# Connector.net
KiCad netlist of a schematic drawn in Altium Designer
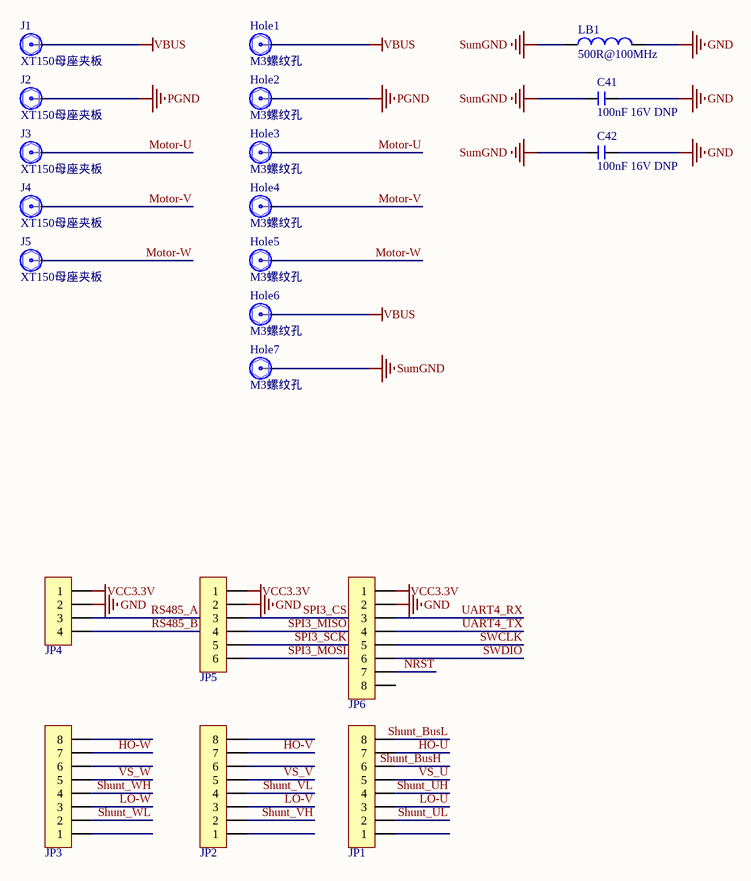
[diagram p0: Connector.SchDoc]

(export (version "E")
  (design (tool "Eeschema 10.0.6"))
  (components
    (comp (ref "C41")
      (value "100nF 16V DNP")
      (footprint "C0603_L")
      (description "独石电容")
      (fields (field (name "版权归属") "源创客"))
      (libsource (lib "Capacitor") (part "C-MLCC"))
    )
    (comp (ref "C42")
      (value "100nF 16V DNP")
      (footprint "C0603_L")
      (description "独石电容")
      (fields (field (name "版权归属") "源创客"))
      (libsource (lib "Capacitor") (part "C-MLCC"))
    )
    (comp (ref "Hole1") (value "M3螺纹孔") (footprint "M3_3*7载流孔_铜柱") (libsource (lib "Hole") (part "M3螺纹孔")))
    (comp (ref "Hole2") (value "M3螺纹孔") (footprint "M3_3*7载流孔_铜柱") (libsource (lib "Hole") (part "M3螺纹孔")))
    (comp (ref "Hole3") (value "M3螺纹孔") (footprint "M3_3*7载流孔_螺丝") (libsource (lib "Hole") (part "M3螺纹孔")))
    (comp (ref "Hole4") (value "M3螺纹孔") (footprint "M3_3*7载流孔_螺丝") (libsource (lib "Hole") (part "M3螺纹孔")))
    (comp (ref "Hole5") (value "M3螺纹孔") (footprint "M3_3*7载流孔_螺丝") (libsource (lib "Hole") (part "M3螺纹孔")))
    (comp (ref "Hole6") (value "M3螺纹孔") (footprint "M3_3*7载流孔_铜柱") (libsource (lib "Hole") (part "M3螺纹孔")))
    (comp (ref "Hole7") (value "M3螺纹孔") (footprint "M3_3*7载流孔_铜柱") (libsource (lib "Hole") (part "M3螺纹孔")))
    (comp (ref "J1")
      (value "XT150母座夹板")
      (footprint "XT150_母座夹板 - VBUS")
      (libsource (lib "Connector-PWR") (part "XT150母座夹板"))
    )
    (comp (ref "J2")
      (value "XT150母座夹板")
      (footprint "XT150_母座夹板 - PGND")
      (libsource (lib "Connector-PWR") (part "XT150母座夹板"))
    )
    (comp (ref "J3")
      (value "XT150母座夹板")
      (footprint "XT150_母座夹板 - duplicate")
      (libsource (lib "Connector-PWR") (part "XT150母座夹板"))
    )
    (comp (ref "J4")
      (value "XT150母座夹板")
      (footprint "XT150_母座夹板")
      (libsource (lib "Connector-PWR") (part "XT150母座夹板"))
    )
    (comp (ref "J5")
      (value "XT150母座夹板")
      (footprint "XT150_母座夹板")
      (libsource (lib "Connector-PWR") (part "XT150母座夹板"))
    )
    (comp (ref "JP1")
      (value "HDR-1X8")
      (footprint "贴片排母2.54mm_交错_8P - 正脚位")
      (description "8P接插件")
      (fields (field (name "版权归属") "源创客"))
      (libsource (lib "Connector-PinHeader") (part "Header 8"))
    )
    (comp (ref "JP2")
      (value "HDR-1X8")
      (footprint "贴片排母2.54mm_交错_7P - 正脚位")
      (description "8P接插件")
      (fields (field (name "版权归属") "源创客"))
      (libsource (lib "Connector-PinHeader") (part "Header 8"))
    )
    (comp (ref "JP3")
      (value "HDR-1X8")
      (footprint "贴片排母2.54mm_交错_7P - 正脚位")
      (description "8P接插件")
      (fields (field (name "版权归属") "源创客"))
      (libsource (lib "Connector-PinHeader") (part "Header 8"))
    )
    (comp (ref "JP4")
      (value "HDR-1X4")
      (footprint "MX 1.25-WS-4P")
      (description "4P接插件")
      (fields (field (name "版权归属") "源创客"))
      (libsource (lib "Connector-PinHeader") (part "Header 4"))
    )
    (comp (ref "JP5")
      (value "HDR-1X6")
      (footprint "MX 1.25-WS-6P")
      (description "6P接插件")
      (fields (field (name "版权归属") "源创客"))
      (libsource (lib "Connector-PinHeader") (part "Header 6"))
    )
    (comp (ref "JP6")
      (value "HDR-1X8")
      (footprint "MX 1.25-WS-8P")
      (description "8P接插件")
      (fields (field (name "版权归属") "源创客"))
      (libsource (lib "") (part "Header 8_1"))
    )
    (comp (ref "LB1")
      (value "500R@100MHz")
      (footprint "FB 0805_L")
      (description "磁珠")
      (fields (field (name "版权归属") "源创客"))
      (libsource (lib "Inductor") (part "LB"))
    )
  )
  (nets
    (net (code "1") (name "/HO-U") (class "Default")
      (node (ref "JP1") (pin "7") (pinfunction "7_7") (pintype "passive"))
    )
    (net (code "2") (name "/HO-V") (class "Default")
      (node (ref "JP2") (pin "7") (pinfunction "7_7") (pintype "passive"))
    )
    (net (code "3") (name "/HO-W") (class "Default")
      (node (ref "JP3") (pin "7") (pinfunction "7_7") (pintype "passive"))
    )
    (net (code "4") (name "/LO-U") (class "Default")
      (node (ref "JP1") (pin "3") (pinfunction "3_3") (pintype "passive"))
    )
    (net (code "5") (name "/LO-V") (class "Default")
      (node (ref "JP2") (pin "3") (pinfunction "3_3") (pintype "passive"))
    )
    (net (code "6") (name "/LO-W") (class "Default")
      (node (ref "JP3") (pin "3") (pinfunction "3_3") (pintype "passive"))
    )
    (net (code "7") (name "/Motor-U") (class "Default")
      (node (ref "Hole3") (pin "1") (pinfunction "1_1") (pintype "passive"))
      (node (ref "J3") (pin "1") (pinfunction "1_1") (pintype "passive"))
    )
    (net (code "8") (name "/Motor-V") (class "Default")
      (node (ref "Hole4") (pin "1") (pinfunction "1_1") (pintype "passive"))
      (node (ref "J4") (pin "1") (pinfunction "1_1") (pintype "passive"))
    )
    (net (code "9") (name "/Motor-W") (class "Default")
      (node (ref "Hole5") (pin "1") (pinfunction "1_1") (pintype "passive"))
      (node (ref "J5") (pin "1") (pinfunction "1_1") (pintype "passive"))
    )
    (net (code "10") (name "/NRST") (class "Default")
      (node (ref "JP6") (pin "7") (pinfunction "7_7") (pintype "passive"))
    )
    (net (code "11") (name "/RS485_A") (class "Default")
      (node (ref "JP4") (pin "3") (pinfunction "3_3") (pintype "passive"))
    )
    (net (code "12") (name "/RS485_B") (class "Default")
      (node (ref "JP4") (pin "4") (pinfunction "4_4") (pintype "passive"))
    )
    (net (code "13") (name "/SPI3_CS") (class "Default")
      (node (ref "JP5") (pin "3") (pinfunction "3_3") (pintype "passive"))
    )
    (net (code "14") (name "/SPI3_MISO") (class "Default")
      (node (ref "JP5") (pin "4") (pinfunction "4_4") (pintype "passive"))
    )
    (net (code "15") (name "/SPI3_MOSI") (class "Default")
      (node (ref "JP5") (pin "6") (pinfunction "6_6") (pintype "passive"))
    )
    (net (code "16") (name "/SPI3_SCK") (class "Default")
      (node (ref "JP5") (pin "5") (pinfunction "5_5") (pintype "passive"))
    )
    (net (code "17") (name "/SWCLK") (class "Default")
      (node (ref "JP6") (pin "5") (pinfunction "5_5") (pintype "passive"))
    )
    (net (code "18") (name "/SWDIO") (class "Default")
      (node (ref "JP6") (pin "6") (pinfunction "6_6") (pintype "passive"))
    )
    (net (code "19") (name "/Shunt_BusH") (class "Default")
      (node (ref "JP1") (pin "6") (pinfunction "6_6") (pintype "passive"))
    )
    (net (code "20") (name "/Shunt_BusL") (class "Default")
      (node (ref "JP1") (pin "8") (pinfunction "8_8") (pintype "passive"))
    )
    (net (code "21") (name "/Shunt_UH") (class "Default")
      (node (ref "JP1") (pin "4") (pinfunction "4_4") (pintype "passive"))
    )
    (net (code "22") (name "/Shunt_UL") (class "Default")
      (node (ref "JP1") (pin "2") (pinfunction "2_2") (pintype "passive"))
    )
    (net (code "23") (name "/Shunt_VH") (class "Default")
      (node (ref "JP2") (pin "2") (pinfunction "2_2") (pintype "passive"))
    )
    (net (code "24") (name "/Shunt_VL") (class "Default")
      (node (ref "JP2") (pin "4") (pinfunction "4_4") (pintype "passive"))
    )
    (net (code "25") (name "/Shunt_WH") (class "Default")
      (node (ref "JP3") (pin "4") (pinfunction "4_4") (pintype "passive"))
    )
    (net (code "26") (name "/Shunt_WL") (class "Default")
      (node (ref "JP3") (pin "2") (pinfunction "2_2") (pintype "passive"))
    )
    (net (code "27") (name "/UART4_RX") (class "Default")
      (node (ref "JP6") (pin "3") (pinfunction "3_3") (pintype "passive"))
    )
    (net (code "28") (name "/UART4_TX") (class "Default")
      (node (ref "JP6") (pin "4") (pinfunction "4_4") (pintype "passive"))
    )
    (net (code "29") (name "/VS_U") (class "Default")
      (node (ref "JP1") (pin "5") (pinfunction "5_5") (pintype "passive"))
    )
    (net (code "30") (name "/VS_V") (class "Default")
      (node (ref "JP2") (pin "5") (pinfunction "5_5") (pintype "passive"))
    )
    (net (code "31") (name "/VS_W") (class "Default")
      (node (ref "JP3") (pin "5") (pinfunction "5_5") (pintype "passive"))
    )
    (net (code "32") (name "GND") (class "Default")
      (node (ref "C41") (pin "1") (pinfunction "1_1") (pintype "passive"))
      (node (ref "C42") (pin "1") (pinfunction "1_1") (pintype "passive"))
      (node (ref "JP4") (pin "2") (pinfunction "2_2") (pintype "passive"))
      (node (ref "JP5") (pin "2") (pinfunction "2_2") (pintype "passive"))
      (node (ref "JP6") (pin "2") (pinfunction "2_2") (pintype "passive"))
      (node (ref "LB1") (pin "2") (pinfunction "2_2") (pintype "passive"))
    )
    (net (code "33") (name "PGND") (class "Default")
      (node (ref "Hole2") (pin "1") (pinfunction "1_1") (pintype "passive"))
      (node (ref "J2") (pin "1") (pinfunction "1_1") (pintype "passive"))
    )
    (net (code "34") (name "SumGND") (class "Default")
      (node (ref "C41") (pin "2") (pinfunction "2_2") (pintype "passive"))
      (node (ref "C42") (pin "2") (pinfunction "2_2") (pintype "passive"))
      (node (ref "Hole7") (pin "1") (pinfunction "1_1") (pintype "passive"))
      (node (ref "LB1") (pin "1") (pinfunction "1_1") (pintype "passive"))
    )
    (net (code "35") (name "VBUS") (class "Default")
      (node (ref "Hole1") (pin "1") (pinfunction "1_1") (pintype "passive"))
      (node (ref "Hole6") (pin "1") (pinfunction "1_1") (pintype "passive"))
      (node (ref "J1") (pin "1") (pinfunction "1_1") (pintype "passive"))
    )
    (net (code "36") (name "VCC3.3V") (class "Default")
      (node (ref "JP4") (pin "1") (pinfunction "1_1") (pintype "passive"))
      (node (ref "JP5") (pin "1") (pinfunction "1_1") (pintype "passive"))
      (node (ref "JP6") (pin "1") (pinfunction "1_1") (pintype "passive"))
    )
    (net (code "37") (name "unconnected-(JP1-Pad1)") (class "Default")
      (node (ref "JP1") (pin "1") (pinfunction "1_1") (pintype "passive"))
    )
    (net (code "38") (name "unconnected-(JP2-Pad1)") (class "Default")
      (node (ref "JP2") (pin "1") (pinfunction "1_1") (pintype "passive"))
    )
    (net (code "39") (name "unconnected-(JP2-Pad6)") (class "Default")
      (node (ref "JP2") (pin "6") (pinfunction "6_6") (pintype "passive"))
    )
    (net (code "40") (name "unconnected-(JP2-Pad8)") (class "Default")
      (node (ref "JP2") (pin "8") (pinfunction "8_8") (pintype "passive"))
    )
    (net (code "41") (name "unconnected-(JP3-Pad1)") (class "Default")
      (node (ref "JP3") (pin "1") (pinfunction "1_1") (pintype "passive"))
    )
    (net (code "42") (name "unconnected-(JP3-Pad6)") (class "Default")
      (node (ref "JP3") (pin "6") (pinfunction "6_6") (pintype "passive"))
    )
    (net (code "43") (name "unconnected-(JP3-Pad8)") (class "Default")
      (node (ref "JP3") (pin "8") (pinfunction "8_8") (pintype "passive"))
    )
    (net (code "44") (name "unconnected-(JP6-Pad8)") (class "Default")
      (node (ref "JP6") (pin "8") (pinfunction "8_8") (pintype "passive"))
    )
  )
)
